# linearni_zdroj.net
KiCad netlist of a schematic drawn in EAGLE
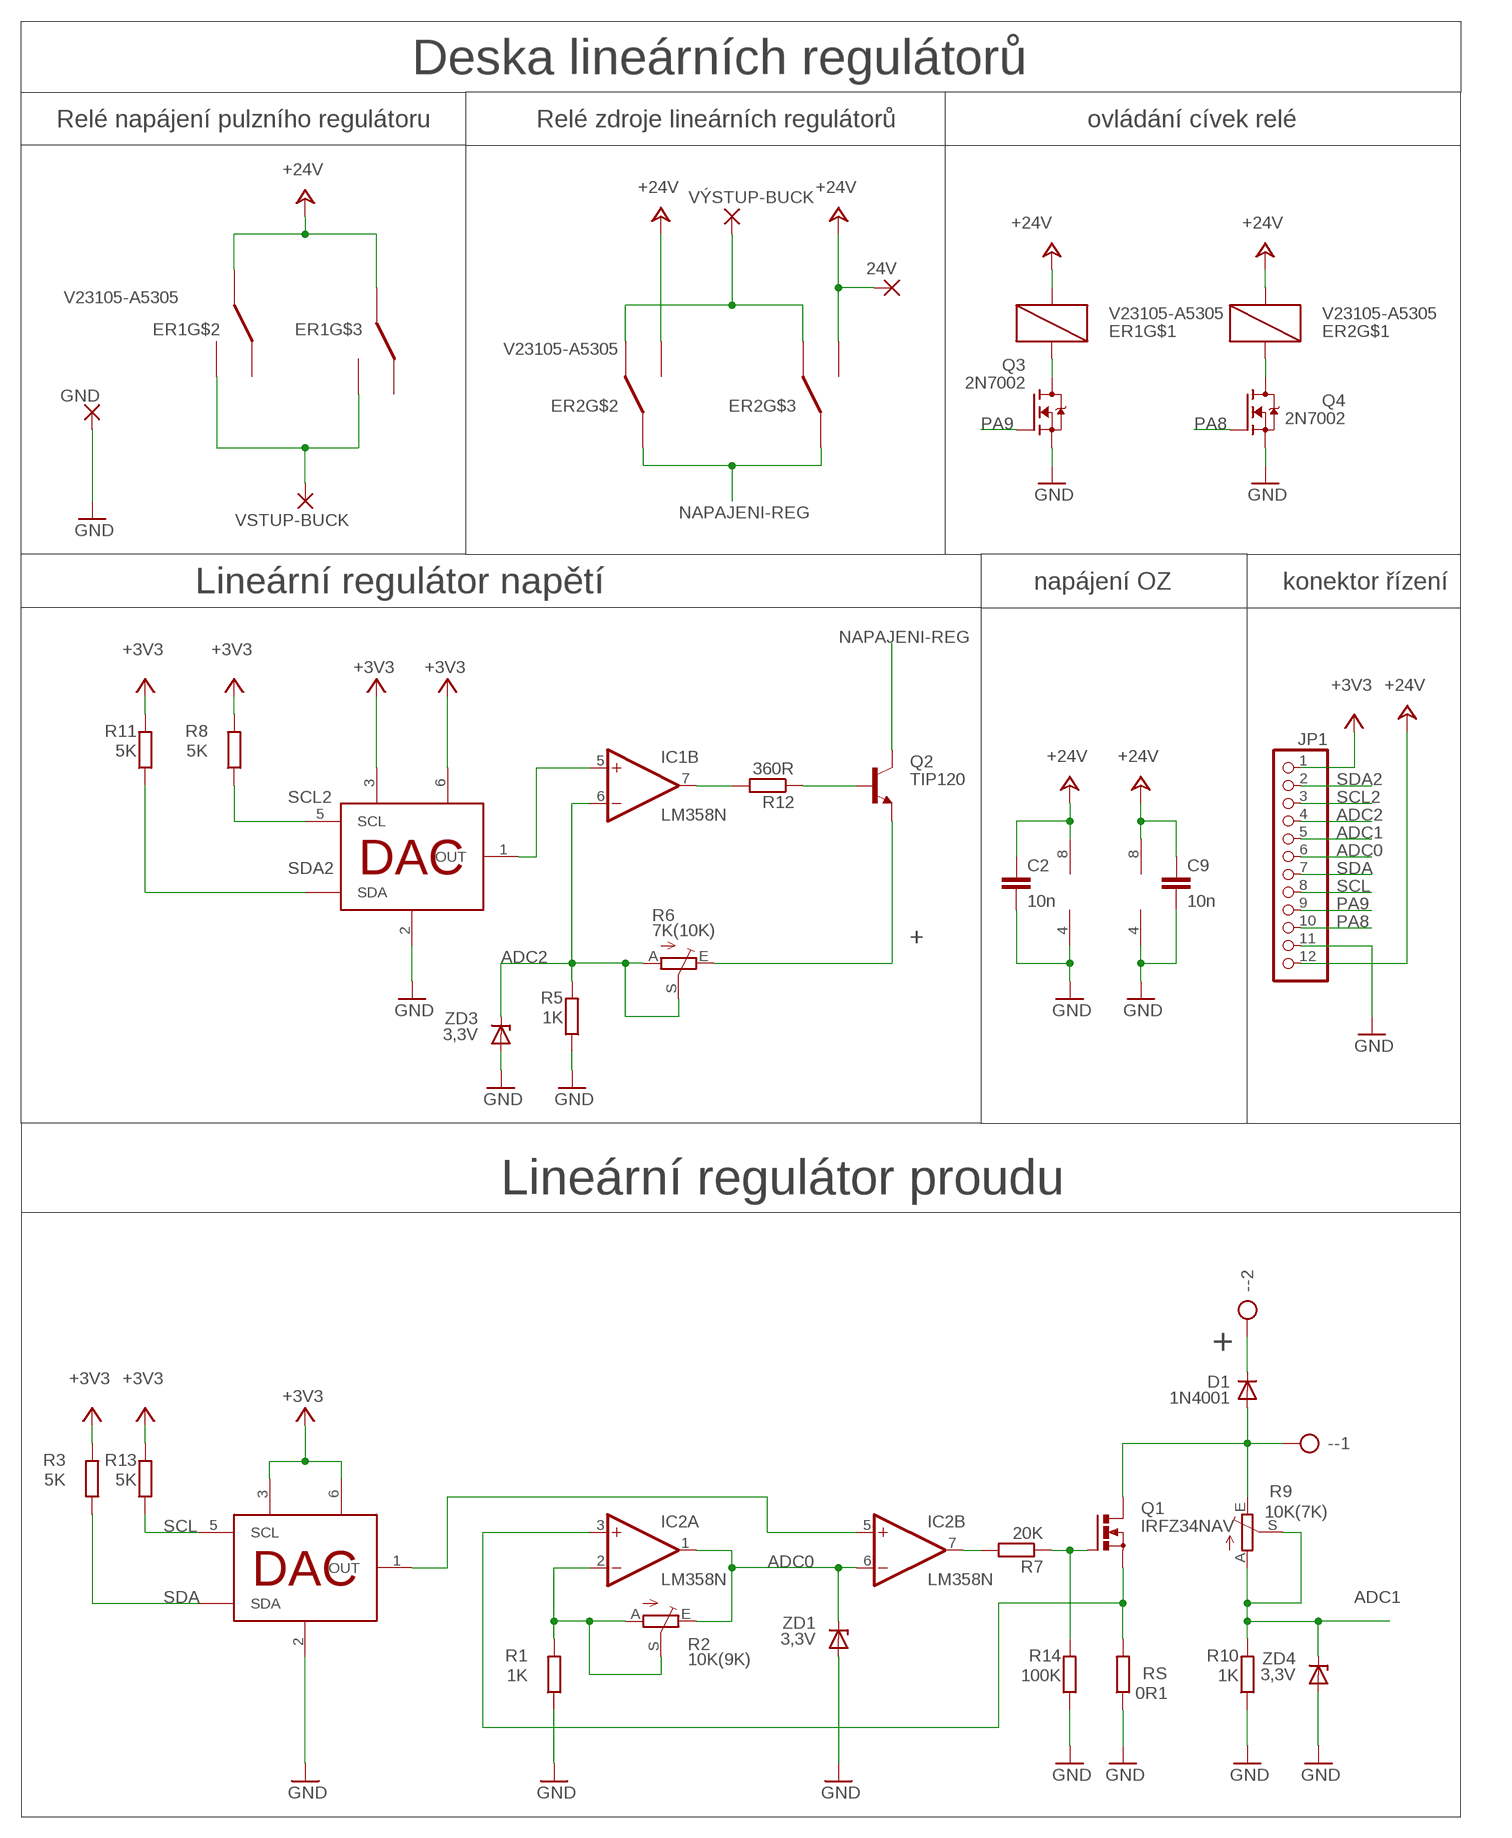
[diagram p0: schematic, sheet 1]

(export (version "E")
  (design (tool "Eeschema 10.0.6"))
  (components
    (comp (ref "-")
      (value "AK500/2")
      (footprint "eagle-import:AK500_2")
      (libsource (lib "eagle-import") (part "AK500/2"))
    )
    (comp (ref "24V")
      (value "3,81/1,4")
      (footprint "eagle-import:3,81_1,4")
      (libsource (lib "eagle-import") (part "3,81/1,4"))
    )
    (comp (ref "C2")
      (value "10n")
      (footprint "eagle-import:C0805")
      (libsource (lib "eagle-import") (part "C-EUC0805"))
    )
    (comp (ref "C9")
      (value "10n")
      (footprint "eagle-import:C0805")
      (libsource (lib "eagle-import") (part "C-EUC0805"))
    )
    (comp (ref "D1")
      (value "1N4001")
      (footprint "eagle-import:DO35-7B")
      (libsource (lib "eagle-import") (part "DIODE7"))
    )
    (comp (ref "ER1")
      (value "V23105-A5305")
      (footprint "eagle-import:V23105-A5305-A201")
      (libsource (lib "eagle-import") (part "V23105-A5305-A201"))
    )
    (comp (ref "ER2")
      (value "V23105-A5305")
      (footprint "eagle-import:V23105-A5305-A201")
      (libsource (lib "eagle-import") (part "V23105-A5305-A201"))
    )
    (comp (ref "GND")
      (value "3,81/1,4")
      (footprint "eagle-import:3,81_1,4")
      (libsource (lib "eagle-import") (part "3,81/1,4"))
    )
    (comp (ref "IC1")
      (value "LM358N")
      (footprint "eagle-import:DIL08")
      (libsource (lib "eagle-import") (part "LM358N"))
    )
    (comp (ref "IC2")
      (value "LM358N")
      (footprint "eagle-import:DIL08")
      (libsource (lib "eagle-import") (part "LM358N"))
    )
    (comp (ref "JP1")
      (value "PINHD-1X12")
      (footprint "eagle-import:1X12")
      (libsource (lib "eagle-import") (part "PINHD-1X12"))
    )
    (comp (ref "Q1")
      (value "IRFZ34NAV")
      (footprint "eagle-import:TO220AV")
      (libsource (lib "eagle-import") (part "IRFZ34NAV"))
    )
    (comp (ref "Q2")
      (value "TIP120")
      (footprint "eagle-import:TO220V")
      (libsource (lib "eagle-import") (part "-NPN-TO220V"))
    )
    (comp (ref "Q3")
      (value "2N7002")
      (footprint "eagle-import:SOT95P240X110-3N")
      (libsource (lib "eagle-import") (part "NX3008"))
    )
    (comp (ref "Q4")
      (value "2N7002")
      (footprint "eagle-import:SOT95P240X110-3N")
      (libsource (lib "eagle-import") (part "NX3008"))
    )
    (comp (ref "R1")
      (value "1K")
      (footprint "eagle-import:R0805")
      (libsource (lib "eagle-import") (part "R-EU_R0805"))
    )
    (comp (ref "R2")
      (value "10K(9K)")
      (footprint "eagle-import:CA6V")
      (libsource (lib "eagle-import") (part "TRIM_EU-CA6V"))
    )
    (comp (ref "R3")
      (value "5K")
      (footprint "eagle-import:R0805")
      (libsource (lib "eagle-import") (part "R-EU_R0805"))
    )
    (comp (ref "R5")
      (value "1K")
      (footprint "eagle-import:R0805")
      (libsource (lib "eagle-import") (part "R-EU_R0805"))
    )
    (comp (ref "R6")
      (value "7K(10K)")
      (footprint "eagle-import:CA6V")
      (libsource (lib "eagle-import") (part "TRIM_EU-CA6V"))
    )
    (comp (ref "R7")
      (value "20K")
      (footprint "eagle-import:R0805")
      (libsource (lib "eagle-import") (part "R-EU_R0805"))
    )
    (comp (ref "R8")
      (value "5K")
      (footprint "eagle-import:R0805")
      (libsource (lib "eagle-import") (part "R-EU_R0805"))
    )
    (comp (ref "R9")
      (value "10K(7K)")
      (footprint "eagle-import:CA6V")
      (libsource (lib "eagle-import") (part "TRIM_EU-CA6V"))
    )
    (comp (ref "R10")
      (value "1K")
      (footprint "eagle-import:R0805")
      (libsource (lib "eagle-import") (part "R-EU_R0805"))
    )
    (comp (ref "R11")
      (value "5K")
      (footprint "eagle-import:R0805")
      (libsource (lib "eagle-import") (part "R-EU_R0805"))
    )
    (comp (ref "R12")
      (value "360R")
      (footprint "eagle-import:R0805")
      (libsource (lib "eagle-import") (part "R-EU_R0805"))
    )
    (comp (ref "R13")
      (value "5K")
      (footprint "eagle-import:R0805")
      (libsource (lib "eagle-import") (part "R-EU_R0805"))
    )
    (comp (ref "R14")
      (value "100K")
      (footprint "eagle-import:R0805")
      (libsource (lib "eagle-import") (part "R-EU_R0805"))
    )
    (comp (ref "RS")
      (value "0R1")
      (footprint "eagle-import:0411_15")
      (libsource (lib "eagle-import") (part "R-EU_0411/15"))
    )
    (comp (ref "U$5")
      (value "MCP4726")
      (footprint "eagle-import:TSOT23-6")
      (libsource (lib "eagle-import") (part "MCP4726"))
    )
    (comp (ref "U$6")
      (value "MCP4726")
      (footprint "eagle-import:TSOT23-6")
      (libsource (lib "eagle-import") (part "MCP4726"))
    )
    (comp (ref "VSTUP-BUCK")
      (value "3,81/1,4")
      (footprint "eagle-import:3,81_1,4")
      (libsource (lib "eagle-import") (part "3,81/1,4"))
    )
    (comp (ref "VÝSTUP-BUCK")
      (value "3,81/1,4")
      (footprint "eagle-import:3,81_1,4")
      (libsource (lib "eagle-import") (part "3,81/1,4"))
    )
    (comp (ref "ZD1")
      (value "3,3V")
      (footprint "eagle-import:MINIMELF")
      (libsource (lib "eagle-import") (part "DIODE_ZENER{dblquote}2"))
    )
    (comp (ref "ZD3")
      (value "3,3V")
      (footprint "eagle-import:MINIMELF")
      (libsource (lib "eagle-import") (part "DIODE_ZENER{dblquote}2"))
    )
    (comp (ref "ZD4")
      (value "3,3V")
      (footprint "eagle-import:MINIMELF")
      (libsource (lib "eagle-import") (part "DIODE_ZENER{dblquote}2"))
    )
  )
  (nets
    (net (code "1") (name "+3V3") (class "Default")
      (node (ref "JP1") (pin "1") (pinfunction "1_1") (pintype "passive"))
      (node (ref "R11") (pin "2") (pinfunction "2_2") (pintype "passive"))
      (node (ref "R13") (pin "2") (pinfunction "2_2") (pintype "passive"))
      (node (ref "R3") (pin "2") (pinfunction "2_2") (pintype "passive"))
      (node (ref "R8") (pin "2") (pinfunction "2_2") (pintype "passive"))
      (node (ref "U$5") (pin "3") (pinfunction "VDD_3") (pintype "bidirectional"))
      (node (ref "U$5") (pin "6") (pinfunction "VREF_6") (pintype "bidirectional"))
      (node (ref "U$6") (pin "3") (pinfunction "VDD_3") (pintype "bidirectional"))
      (node (ref "U$6") (pin "6") (pinfunction "VREF_6") (pintype "bidirectional"))
    )
    (net (code "2") (name "+24V") (class "Default")
      (node (ref "24V") (pin "1") (pinfunction "P_1") (pintype "passive"))
      (node (ref "C2") (pin "1") (pinfunction "1_1") (pintype "passive"))
      (node (ref "C9") (pin "1") (pinfunction "1_1") (pintype "passive"))
      (node (ref "ER1") (pin "1") (pinfunction "C$1_1") (pintype "input"))
      (node (ref "ER1") (pin "13") (pinfunction "1_13") (pintype "bidirectional"))
      (node (ref "ER1") (pin "4") (pinfunction "1_4") (pintype "bidirectional"))
      (node (ref "ER2") (pin "1") (pinfunction "C$1_1") (pintype "input"))
      (node (ref "ER2") (pin "8") (pinfunction "3_8") (pintype "bidirectional"))
      (node (ref "ER2") (pin "9") (pinfunction "3_9") (pintype "bidirectional"))
      (node (ref "IC1") (pin "8") (pinfunction "V+_8") (pintype "power_in"))
      (node (ref "IC2") (pin "8") (pinfunction "V+_8") (pintype "power_in"))
      (node (ref "JP1") (pin "12") (pinfunction "12_12") (pintype "passive"))
    )
    (net (code "3") (name "/+") (class "Default")
      (node (ref "-") (pin "2") (pinfunction "KL_2") (pintype "passive"))
      (node (ref "D1") (pin "C") (pinfunction "C_C") (pintype "passive"))
      (node (ref "Q2") (pin "3") (pinfunction "E_3") (pintype "passive"))
      (node (ref "R6") (pin "E") (pinfunction "E_E") (pintype "passive"))
    )
    (net (code "4") (name "/ADC0") (class "Default")
      (node (ref "IC2") (pin "1") (pinfunction "OUT_1") (pintype "output"))
      (node (ref "IC2") (pin "6") (pinfunction "-IN_6") (pintype "input"))
      (node (ref "JP1") (pin "6") (pinfunction "6_6") (pintype "passive"))
      (node (ref "R2") (pin "E") (pinfunction "E_E") (pintype "passive"))
      (node (ref "ZD1") (pin "C") (pinfunction "C_C") (pintype "passive"))
    )
    (net (code "5") (name "/ADC1") (class "Default")
      (node (ref "JP1") (pin "5") (pinfunction "5_5") (pintype "passive"))
      (node (ref "R10") (pin "2") (pinfunction "2_2") (pintype "passive"))
      (node (ref "R9") (pin "A") (pinfunction "A_A") (pintype "passive"))
      (node (ref "R9") (pin "S") (pinfunction "S_S") (pintype "passive"))
      (node (ref "ZD4") (pin "C") (pinfunction "C_C") (pintype "passive"))
    )
    (net (code "6") (name "/ADC2") (class "Default")
      (node (ref "IC1") (pin "6") (pinfunction "-IN_6") (pintype "input"))
      (node (ref "JP1") (pin "4") (pinfunction "4_4") (pintype "passive"))
      (node (ref "R5") (pin "2") (pinfunction "2_2") (pintype "passive"))
      (node (ref "R6") (pin "A") (pinfunction "A_A") (pintype "passive"))
      (node (ref "R6") (pin "S") (pinfunction "S_S") (pintype "passive"))
      (node (ref "ZD3") (pin "C") (pinfunction "C_C") (pintype "passive"))
    )
    (net (code "7") (name "/NAPAJENI-REG") (class "Default")
      (node (ref "ER2") (pin "13") (pinfunction "1_13") (pintype "bidirectional"))
      (node (ref "ER2") (pin "4") (pinfunction "1_4") (pintype "bidirectional"))
      (node (ref "Q2") (pin "2") (pinfunction "C_2") (pintype "passive"))
    )
    (net (code "8") (name "/PA8") (class "Default")
      (node (ref "JP1") (pin "10") (pinfunction "10_10") (pintype "passive"))
      (node (ref "Q4") (pin "1") (pinfunction "G_1") (pintype "passive"))
    )
    (net (code "9") (name "/PA9") (class "Default")
      (node (ref "JP1") (pin "9") (pinfunction "9_9") (pintype "passive"))
      (node (ref "Q3") (pin "1") (pinfunction "G_1") (pintype "passive"))
    )
    (net (code "10") (name "/SCL") (class "Default")
      (node (ref "JP1") (pin "8") (pinfunction "8_8") (pintype "passive"))
      (node (ref "R13") (pin "1") (pinfunction "1_1") (pintype "passive"))
      (node (ref "U$5") (pin "5") (pinfunction "SCL_5") (pintype "bidirectional"))
    )
    (net (code "11") (name "/SCL2") (class "Default")
      (node (ref "JP1") (pin "3") (pinfunction "3_3") (pintype "passive"))
      (node (ref "R8") (pin "1") (pinfunction "1_1") (pintype "passive"))
      (node (ref "U$6") (pin "5") (pinfunction "SCL_5") (pintype "bidirectional"))
    )
    (net (code "12") (name "/SDA") (class "Default")
      (node (ref "JP1") (pin "7") (pinfunction "7_7") (pintype "passive"))
      (node (ref "R3") (pin "1") (pinfunction "1_1") (pintype "passive"))
      (node (ref "U$5") (pin "4") (pinfunction "SDA_4") (pintype "bidirectional"))
    )
    (net (code "13") (name "/SDA2") (class "Default")
      (node (ref "JP1") (pin "2") (pinfunction "2_2") (pintype "passive"))
      (node (ref "R11") (pin "1") (pinfunction "1_1") (pintype "passive"))
      (node (ref "U$6") (pin "4") (pinfunction "SDA_4") (pintype "bidirectional"))
    )
    (net (code "14") (name "GND") (class "Default")
      (node (ref "C2") (pin "2") (pinfunction "2_2") (pintype "passive"))
      (node (ref "C9") (pin "2") (pinfunction "2_2") (pintype "passive"))
      (node (ref "GND") (pin "1") (pinfunction "P_1") (pintype "passive"))
      (node (ref "IC1") (pin "4") (pinfunction "V-_4") (pintype "power_in"))
      (node (ref "IC2") (pin "4") (pinfunction "V-_4") (pintype "power_in"))
      (node (ref "JP1") (pin "11") (pinfunction "11_11") (pintype "passive"))
      (node (ref "Q3") (pin "2") (pinfunction "S_2") (pintype "passive"))
      (node (ref "Q4") (pin "2") (pinfunction "S_2") (pintype "passive"))
      (node (ref "R1") (pin "1") (pinfunction "1_1") (pintype "passive"))
      (node (ref "R10") (pin "1") (pinfunction "1_1") (pintype "passive"))
      (node (ref "R14") (pin "1") (pinfunction "1_1") (pintype "passive"))
      (node (ref "R5") (pin "1") (pinfunction "1_1") (pintype "passive"))
      (node (ref "RS") (pin "1") (pinfunction "1_1") (pintype "passive"))
      (node (ref "U$5") (pin "2") (pinfunction "VSS_2") (pintype "bidirectional"))
      (node (ref "U$6") (pin "2") (pinfunction "VSS_2") (pintype "bidirectional"))
      (node (ref "ZD1") (pin "A") (pinfunction "A_A") (pintype "passive"))
      (node (ref "ZD3") (pin "A") (pinfunction "A_A") (pintype "passive"))
      (node (ref "ZD4") (pin "A") (pinfunction "A_A") (pintype "passive"))
    )
    (net (code "15") (name "Net-(-A-KL)") (class "Default")
      (node (ref "-") (pin "1") (pinfunction "KL_1") (pintype "passive"))
      (node (ref "D1") (pin "A") (pinfunction "A_A") (pintype "passive"))
      (node (ref "Q1") (pin "D") (pinfunction "D_D") (pintype "passive"))
      (node (ref "R9") (pin "E") (pinfunction "E_E") (pintype "passive"))
    )
    (net (code "16") (name "Net-(ER1A-C$2)") (class "Default")
      (node (ref "ER1") (pin "16") (pinfunction "C$2_16") (pintype "input"))
      (node (ref "Q3") (pin "3") (pinfunction "D_3") (pintype "passive"))
    )
    (net (code "17") (name "Net-(ER1B-3)") (class "Default")
      (node (ref "ER1") (pin "8") (pinfunction "3_8") (pintype "bidirectional"))
      (node (ref "ER1") (pin "9") (pinfunction "3_9") (pintype "bidirectional"))
      (node (ref "VSTUP-BUCK") (pin "1") (pinfunction "P_1") (pintype "passive"))
    )
    (net (code "18") (name "Net-(ER2A-C$2)") (class "Default")
      (node (ref "ER2") (pin "16") (pinfunction "C$2_16") (pintype "input"))
      (node (ref "Q4") (pin "3") (pinfunction "D_3") (pintype "passive"))
    )
    (net (code "19") (name "Net-(ER2B-2)") (class "Default")
      (node (ref "ER2") (pin "11") (pinfunction "2_11") (pintype "bidirectional"))
      (node (ref "ER2") (pin "6") (pinfunction "2_6") (pintype "bidirectional"))
      (node (ref "VÝSTUP-BUCK") (pin "1") (pinfunction "P_1") (pintype "passive"))
    )
    (net (code "20") (name "Net-(IC1B-+IN)") (class "Default")
      (node (ref "IC1") (pin "5") (pinfunction "+IN_5") (pintype "input"))
      (node (ref "U$6") (pin "1") (pinfunction "OUT_1") (pintype "bidirectional"))
    )
    (net (code "21") (name "Net-(IC1B-OUT)") (class "Default")
      (node (ref "IC1") (pin "7") (pinfunction "OUT_7") (pintype "output"))
      (node (ref "R12") (pin "2") (pinfunction "2_2") (pintype "passive"))
    )
    (net (code "22") (name "Net-(IC2A-+IN)") (class "Default")
      (node (ref "IC2") (pin "3") (pinfunction "+IN_3") (pintype "input"))
      (node (ref "Q1") (pin "S") (pinfunction "S_S") (pintype "passive"))
      (node (ref "RS") (pin "2") (pinfunction "2_2") (pintype "passive"))
    )
    (net (code "23") (name "Net-(IC2A--IN)") (class "Default")
      (node (ref "IC2") (pin "2") (pinfunction "-IN_2") (pintype "input"))
      (node (ref "R1") (pin "2") (pinfunction "2_2") (pintype "passive"))
      (node (ref "R2") (pin "A") (pinfunction "A_A") (pintype "passive"))
      (node (ref "R2") (pin "S") (pinfunction "S_S") (pintype "passive"))
    )
    (net (code "24") (name "Net-(IC2B-+IN)") (class "Default")
      (node (ref "IC2") (pin "5") (pinfunction "+IN_5") (pintype "input"))
      (node (ref "U$5") (pin "1") (pinfunction "OUT_1") (pintype "bidirectional"))
    )
    (net (code "25") (name "Net-(IC2B-OUT)") (class "Default")
      (node (ref "IC2") (pin "7") (pinfunction "OUT_7") (pintype "output"))
      (node (ref "R7") (pin "2") (pinfunction "2_2") (pintype "passive"))
    )
    (net (code "26") (name "Net-(Q1-PadG)") (class "Default")
      (node (ref "Q1") (pin "G") (pinfunction "G_G") (pintype "passive"))
      (node (ref "R14") (pin "2") (pinfunction "2_2") (pintype "passive"))
      (node (ref "R7") (pin "1") (pinfunction "1_1") (pintype "passive"))
    )
    (net (code "27") (name "Net-(Q2-B)") (class "Default")
      (node (ref "Q2") (pin "1") (pinfunction "B_1") (pintype "passive"))
      (node (ref "R12") (pin "1") (pinfunction "1_1") (pintype "passive"))
    )
    (net (code "28") (name "unconnected-(ER1B-2-Pad6)") (class "Default")
      (node (ref "ER1") (pin "6") (pinfunction "2_6") (pintype "bidirectional"))
    )
    (net (code "29") (name "unconnected-(ER1C-2-Pad11)") (class "Default")
      (node (ref "ER1") (pin "11") (pinfunction "2_11") (pintype "bidirectional"))
    )
  )
)
